# Stm32_sch.net
KiCad netlist of a schematic drawn in Altium Designer
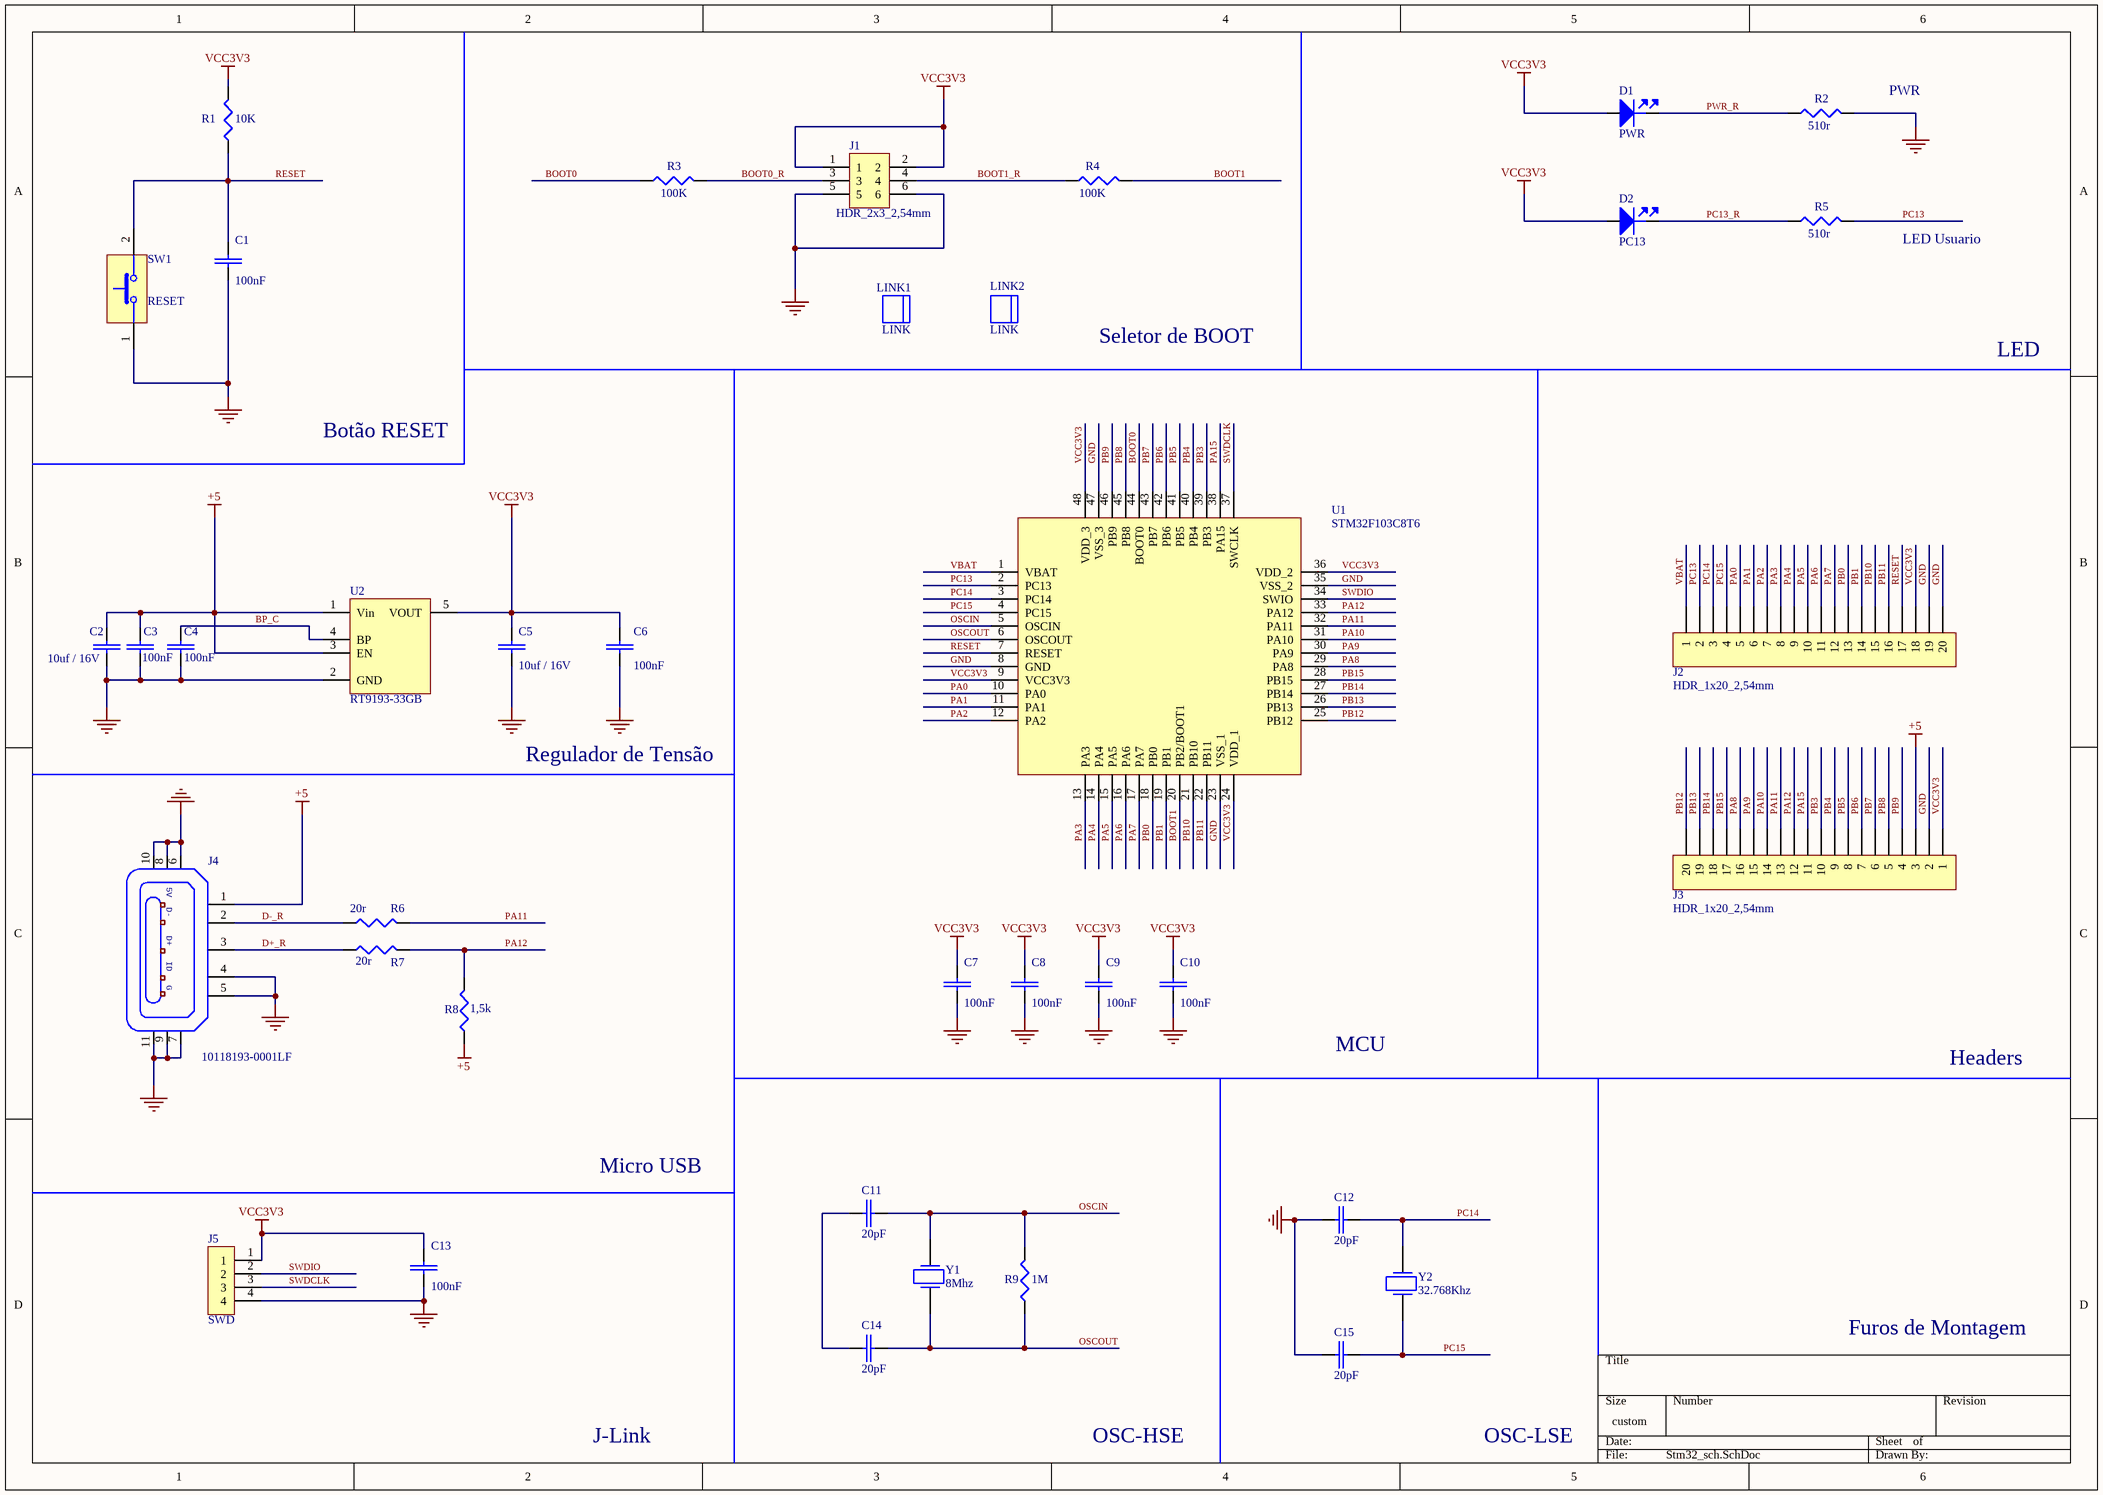
[diagram p0: Stm32_sch.SchDoc]

(export (version "E")
  (design (tool "Eeschema 10.0.6"))
  (components
    (comp (ref "C1")
      (value "100nF")
      (footprint "CP-0603")
      (description "Multilayer Ceramic Capacitors (MLCC) - SMD/SMT 50volts 0.1uF X7R 10%")
      (fields
        (field (name "MANUFACTURER") "KEMET")
        (field (name "MANUFACTURER PART NUMBER") "C0603C104K5RACTU")
      )
      (libsource (lib "Stm32_lib") (part "C-0603_100nF"))
    )
    (comp (ref "C2")
      (value "10uf / 16V")
      (footprint "CP_0805")
      (fields
        (field (name "MANUFACTURER") "TDK")
        (field (name "MANUFACTURER PART NUMBER") "C2012X5R1C106M085AC")
        (field (name "TOLERANCE") "20%")
      )
      (libsource (lib "Stm32_lib") (part "C-0805 10uF / 16V"))
    )
    (comp (ref "C3")
      (value "100nF")
      (footprint "CP-0603")
      (description "Multilayer Ceramic Capacitors (MLCC) - SMD/SMT 50volts 0.1uF X7R 10%")
      (fields
        (field (name "MANUFACTURER") "KEMET")
        (field (name "MANUFACTURER PART NUMBER") "C0603C104K5RACTU")
      )
      (libsource (lib "Stm32_lib") (part "C-0603_100nF"))
    )
    (comp (ref "C4")
      (value "100nF")
      (footprint "CP-0603")
      (description "Multilayer Ceramic Capacitors (MLCC) - SMD/SMT 50volts 0.1uF X7R 10%")
      (fields
        (field (name "MANUFACTURER") "KEMET")
        (field (name "MANUFACTURER PART NUMBER") "C0603C104K5RACTU")
      )
      (libsource (lib "Stm32_lib") (part "C-0603_100nF"))
    )
    (comp (ref "C5")
      (value "10uf / 16V")
      (footprint "CP_0805")
      (fields
        (field (name "MANUFACTURER") "TDK")
        (field (name "MANUFACTURER PART NUMBER") "C2012X5R1C106M085AC")
        (field (name "TOLERANCE") "20%")
      )
      (libsource (lib "Stm32_lib") (part "C-0805 10uF / 16V"))
    )
    (comp (ref "C6")
      (value "100nF")
      (footprint "CP-0603")
      (description "Multilayer Ceramic Capacitors (MLCC) - SMD/SMT 50volts 0.1uF X7R 10%")
      (fields
        (field (name "MANUFACTURER") "KEMET")
        (field (name "MANUFACTURER PART NUMBER") "C0603C104K5RACTU")
      )
      (libsource (lib "Stm32_lib") (part "C-0603_100nF"))
    )
    (comp (ref "C7")
      (value "100nF")
      (footprint "CP-0603")
      (description "Multilayer Ceramic Capacitors (MLCC) - SMD/SMT 50volts 0.1uF X7R 10%")
      (fields
        (field (name "MANUFACTURER") "KEMET")
        (field (name "MANUFACTURER PART NUMBER") "C0603C104K5RACTU")
      )
      (libsource (lib "Stm32_lib") (part "C-0603_100nF"))
    )
    (comp (ref "C8")
      (value "100nF")
      (footprint "CP-0603")
      (description "Multilayer Ceramic Capacitors (MLCC) - SMD/SMT 50volts 0.1uF X7R 10%")
      (fields
        (field (name "MANUFACTURER") "KEMET")
        (field (name "MANUFACTURER PART NUMBER") "C0603C104K5RACTU")
      )
      (libsource (lib "Stm32_lib") (part "C-0603_100nF"))
    )
    (comp (ref "C9")
      (value "100nF")
      (footprint "CP-0603")
      (description "Multilayer Ceramic Capacitors (MLCC) - SMD/SMT 50volts 0.1uF X7R 10%")
      (fields
        (field (name "MANUFACTURER") "KEMET")
        (field (name "MANUFACTURER PART NUMBER") "C0603C104K5RACTU")
      )
      (libsource (lib "Stm32_lib") (part "C-0603_100nF"))
    )
    (comp (ref "C10")
      (value "100nF")
      (footprint "CP-0603")
      (description "Multilayer Ceramic Capacitors (MLCC) - SMD/SMT 50volts 0.1uF X7R 10%")
      (fields
        (field (name "MANUFACTURER") "KEMET")
        (field (name "MANUFACTURER PART NUMBER") "C0603C104K5RACTU")
      )
      (libsource (lib "Stm32_lib") (part "C-0603_100nF"))
    )
    (comp (ref "C11")
      (value "20pF")
      (footprint "CP-0603")
      (description "Cap Ceramic 20pF 50V C0G 2% SMD 0603 125°C Paper T/R")
      (fields
        (field (name "MANUFACTURER") "KEMET")
        (field (name "MANUFACTURER PART NUMBER") "C0603C200G5GAC7867")
      )
      (libsource (lib "Stm32_lib") (part "C-0603_20pF"))
    )
    (comp (ref "C12")
      (value "20pF")
      (footprint "CP-0603")
      (description "Cap Ceramic 20pF 50V C0G 2% SMD 0603 125°C Paper T/R")
      (fields
        (field (name "MANUFACTURER") "KEMET")
        (field (name "MANUFACTURER PART NUMBER") "C0603C200G5GAC7867")
      )
      (libsource (lib "Stm32_lib") (part "C-0603_20pF"))
    )
    (comp (ref "C13")
      (value "100nF")
      (footprint "CP-0603")
      (description "Multilayer Ceramic Capacitors (MLCC) - SMD/SMT 50volts 0.1uF X7R 10%")
      (fields
        (field (name "MANUFACTURER") "KEMET")
        (field (name "MANUFACTURER PART NUMBER") "C0603C104K5RACTU")
      )
      (libsource (lib "Stm32_lib") (part "C-0603_100nF"))
    )
    (comp (ref "C14")
      (value "20pF")
      (footprint "CP-0603")
      (description "Cap Ceramic 20pF 50V C0G 2% SMD 0603 125°C Paper T/R")
      (fields
        (field (name "MANUFACTURER") "KEMET")
        (field (name "MANUFACTURER PART NUMBER") "C0603C200G5GAC7867")
      )
      (libsource (lib "Stm32_lib") (part "C-0603_20pF"))
    )
    (comp (ref "C15")
      (value "20pF")
      (footprint "CP-0603")
      (description "Cap Ceramic 20pF 50V C0G 2% SMD 0603 125°C Paper T/R")
      (fields
        (field (name "MANUFACTURER") "KEMET")
        (field (name "MANUFACTURER PART NUMBER") "C0603C200G5GAC7867")
      )
      (libsource (lib "Stm32_lib") (part "C-0603_20pF"))
    )
    (comp (ref "D1")
      (value "PWR")
      (footprint "LED_Green")
      (description "LED Uni-Color Green 2-Pin Chip 0603(1608Metric) T/R")
      (fields
        (field (name "MANUFACTURER") "Osram Opto")
        (field (name "MANUFACTURER PART NUMBER") "LG Q396-PS-35")
      )
      (libsource (lib "Stm32_lib") (part "LED_Green"))
    )
    (comp (ref "D2")
      (value "PC13")
      (footprint "LED_Orange")
      (description "Smartled Orange Lc")
      (fields
        (field (name "MANUFACTURER") "Osram Opto")
        (field (name "MANUFACTURER PART NUMBER") "LOL29K-H2K1-24-Z")
      )
      (libsource (lib "Stm32_lib") (part "LED_Orange"))
    )
    (comp (ref "J1")
      (value "HDR_2x3_2,54mm")
      (footprint "Header Male 2x3 2,54mm")
      (description "2.54mm (0.1\") Pitch DIL Vertical PC Tail Pin Header, 8.5mm mating pin height, tin, 3+3 contacts")
      (fields (field (name "MANUFACTURER") "Harwin") (field (name "MANUFACTURER PART NUMBER") "M20-9970346"))
      (libsource (lib "Stm32_lib") (part "HDR_2x3_2,54mm"))
    )
    (comp (ref "J2")
      (value "HDR_1x20_2,54mm")
      (footprint "HDR_1x20_2,54mm")
      (description "2.54mm (0.1\") Pitch SIL Vertical PC Tail Pin Header, 6.1mm mating pin height, tin, 20 contacts")
      (fields (field (name "MANUFACTURER") "Harwin") (field (name "MANUFACTURER PART NUMBER") "M20-9992046"))
      (libsource (lib "Stm32_lib") (part "HDR_1x20_p1"))
    )
    (comp (ref "J3")
      (value "HDR_1x20_2,54mm")
      (footprint "HDR2_1x20_2,54mm")
      (description "2.54mm (0.1\") Pitch SIL Vertical PC Tail Pin Header, 6.1mm mating pin height, tin, 20 contacts")
      (fields (field (name "MANUFACTURER") "Harwin") (field (name "MANUFACTURER PART NUMBER") "M20-9992046"))
      (libsource (lib "Stm32_lib") (part "HDR_1x20_p2"))
    )
    (comp (ref "J4")
      (value "10118193-0001LF")
      (footprint "Micro-Usb")
      (description "FCI Right Angle Surface Mount Mount Female USB Connector; 100 V ac; 1.8A")
      (fields (field (name "MANUFACTURER") "Amphenol ICC / FCI"))
      (libsource (lib "Stm32_lib") (part "Micro-Usb"))
    )
    (comp (ref "J5")
      (value "SWD")
      (footprint "HDR_M 1x4 2.54mm")
      (description "Conn Unshrouded Header HDR 4 POS 2.54mm Solder ST Top Entry Thru-Hole T/R")
      (fields
        (field (name "MANUFACTURER") "Amphenol ICC / FCI")
        (field (name "MANUFACTURER PART NUMBER") "77311-462K04LF")
      )
      (libsource (lib "Stm32_lib") (part "HDR_1x4_2.54mm"))
    )
    (comp (ref "LINK1")
      (value "LINK")
      (description "2 Position 2.54 mm Centerline Single Circuit Open Top Jumper")
      (fields
        (field (name "MANUFACTURER") "Sullins")
        (field (name "MANUFACTURER PART NUMBER") "QPC02SXGN-RC")
      )
      (libsource (lib "Stm32_lib") (part "COMM_Jumper"))
    )
    (comp (ref "LINK2")
      (value "LINK")
      (description "2 Position 2.54 mm Centerline Single Circuit Open Top Jumper")
      (fields
        (field (name "MANUFACTURER") "Sullins")
        (field (name "MANUFACTURER PART NUMBER") "QPC02SXGN-RC")
      )
      (libsource (lib "Stm32_lib") (part "COMM_Jumper"))
    )
    (comp (ref "R1")
      (value "10K")
      (footprint "R-0603")
      (description "Res Thin Film 0603 10K Ohm 0.5% 0.1W(1/10W) ±50ppm/C Epoxy SMD T/R")
      (fields
        (field (name "MANUFACTURER") "Yageo")
        (field (name "MANUFACTURER PART NUMBER") "RT0603DRE0710KL")
      )
      (libsource (lib "Stm32_lib") (part "R_0603_10K"))
    )
    (comp (ref "R2")
      (value "510r")
      (footprint "R-0603")
      (description "Res Thick Film 0603 510 Ohm 1% 1/10W 100ppm/C Molded SMD Paper T/R")
      (fields
        (field (name "MANUFACTURER") "Yageo")
        (field (name "MANUFACTURER PART NUMBER") "RC0603FR-07510RL")
      )
      (libsource (lib "Stm32_lib") (part "R_0603_510r"))
    )
    (comp (ref "R3")
      (value "100K")
      (footprint "R-0603")
      (description "RES SMD 100K OHM 1% 1/10W 0603")
      (fields
        (field (name "MANUFACTURER") "Yageo")
        (field (name "MANUFACTURER PART NUMBER") "RC0603FR-07100KL")
      )
      (libsource (lib "Stm32_lib") (part "R_0603_100K"))
    )
    (comp (ref "R4")
      (value "100K")
      (footprint "R-0603")
      (description "RES SMD 100K OHM 1% 1/10W 0603")
      (fields
        (field (name "MANUFACTURER") "Yageo")
        (field (name "MANUFACTURER PART NUMBER") "RC0603FR-07100KL")
      )
      (libsource (lib "Stm32_lib") (part "R_0603_100K"))
    )
    (comp (ref "R5")
      (value "510r")
      (footprint "R-0603")
      (description "Res Thick Film 0603 510 Ohm 1% 1/10W 100ppm/C Molded SMD Paper T/R")
      (fields
        (field (name "MANUFACTURER") "Yageo")
        (field (name "MANUFACTURER PART NUMBER") "RC0603FR-07510RL")
      )
      (libsource (lib "Stm32_lib") (part "R_0603_510r"))
    )
    (comp (ref "R6")
      (value "20r")
      (footprint "R-0603")
      (description "Res Thick Film 0603 20 Ohm 1% 0.1W(1/10W) ±100ppm/C Pad SMD T/R")
      (fields
        (field (name "MANUFACTURER") "Yageo")
        (field (name "MANUFACTURER PART NUMBER") "RC0603FR-0720RL")
      )
      (libsource (lib "Stm32_lib") (part "R_0603_20r"))
    )
    (comp (ref "R7")
      (value "20r")
      (footprint "R-0603")
      (description "Res Thick Film 0603 20 Ohm 1% 0.1W(1/10W) ±100ppm/C Pad SMD T/R")
      (fields
        (field (name "MANUFACTURER") "Yageo")
        (field (name "MANUFACTURER PART NUMBER") "RC0603FR-0720RL")
      )
      (libsource (lib "Stm32_lib") (part "R_0603_20r"))
    )
    (comp (ref "R8")
      (value "1,5k")
      (footprint "R-0603")
      (description "Res Thin Film 0603 1.5K Ohm 0.1% 1/10W ±25ppm/°C 0.01% Molded SMD SMD Waffle Pack")
      (fields
        (field (name "MANUFACTURER") "Vishay Dale")
        (field (name "MANUFACTURER PART NUMBER") "M55342E12B1B50RWS")
      )
      (libsource (lib "Stm32_lib") (part "R_0603_1,5k"))
    )
    (comp (ref "R9")
      (value "1M")
      (footprint "R-0603")
      (description "Res Thick Film 0603 1M Ohm 1% 1/10W ±100ppm/°C Molded SMD Paper T/R")
      (fields
        (field (name "MANUFACTURER") "Yageo")
        (field (name "MANUFACTURER PART NUMBER") "RC0603FR-071ML")
      )
      (libsource (lib "Stm32_lib") (part "R_0603_1M"))
    )
    (comp (ref "SW1")
      (value "RESET")
      (footprint "Push Button")
      (description "Switch Tactile N.O. SPST Rectangular Button F-Lead 0.05A 12VDC 2.45N SMD T/R")
      (fields
        (field (name "MANUFACTURER") "ITT C&K")
        (field (name "MANUFACTURER PART NUMBER") "PTS636SK25FSMTRLFS")
      )
      (libsource (lib "Stm32_lib") (part "Button N/O"))
    )
    (comp (ref "U1")
      (value "STM32F103C8T6")
      (footprint "Stm32f1")
      (description "IC MCU 32BIT 64KB FLASH 48LQFP")
      (fields (field (name "MANUFACTURER") "STMicroelectronics"))
      (libsource (lib "Stm32_lib") (part "STM32F103C8T6"))
    )
    (comp (ref "U2")
      (value "RT9193-33GB")
      (footprint "SOT_23_5")
      (description "IC REG LDO 3.3V 0.3A SOT23-5")
      (fields (field (name "MANUFACTURER") "Richtek"))
      (libsource (lib "Stm32_lib") (part "RT9193-33GB"))
    )
    (comp (ref "Y1")
      (value "8Mhz")
      (footprint "CK_8Mhz")
      (description "Crystal 8MHz ±20ppm (Tol) ±50ppm (Stability) 18pF FUND 80Ohm 2-Pin HC-49/US Thru-Hole Bulk")
      (fields
        (field (name "MANUFACTURER") "Abracon")
        (field (name "MANUFACTURER PART NUMBER") "ABL-8.000MHZ-B2")
      )
      (libsource (lib "Stm32_lib") (part "CK_8Mhz"))
    )
    (comp (ref "Y2")
      (value "32.768Khz")
      (footprint "CK_32.768Khz")
      (description "Crystal, Plastic Molded 32.768Khz, 6Pf, 10Ppm-40+85C, 8 X 3.8 X 2.5 Rohs Compliant: Yes")
      (fields
        (field (name "MANUFACTURER") "Abracon")
        (field (name "MANUFACTURER PART NUMBER") "ABS25-32.768KHZ-6-1-T")
      )
      (libsource (lib "Stm32_lib") (part "CK_32.768Khz"))
    )
  )
  (nets
    (net (code "1") (name "+5") (class "Default")
      (node (ref "C2") (pin "2") (pinfunction "2_2") (pintype "passive"))
      (node (ref "C3") (pin "2") (pinfunction "2_2") (pintype "passive"))
      (node (ref "J3") (pin "3") (pinfunction "3_3") (pintype "passive"))
      (node (ref "J4") (pin "1") (pinfunction "1_1") (pintype "passive"))
      (node (ref "R8") (pin "1") (pinfunction "1_1") (pintype "passive"))
      (node (ref "U2") (pin "1") (pinfunction "Vin_1") (pintype "passive"))
      (node (ref "U2") (pin "3") (pinfunction "EN_3") (pintype "passive"))
    )
    (net (code "2") (name "/BOOT0") (class "Default")
      (node (ref "R3") (pin "1") (pinfunction "1_1") (pintype "passive"))
      (node (ref "U1") (pin "44") (pinfunction "BOOT0_44") (pintype "passive"))
    )
    (net (code "3") (name "/BOOT0_R") (class "Default")
      (node (ref "J1") (pin "3") (pinfunction "3_3") (pintype "passive"))
      (node (ref "R3") (pin "2") (pinfunction "2_2") (pintype "passive"))
    )
    (net (code "4") (name "/BOOT1") (class "Default")
      (node (ref "R4") (pin "2") (pinfunction "2_2") (pintype "passive"))
      (node (ref "U1") (pin "20") (pinfunction "PB2/BOOT1_20") (pintype "passive"))
    )
    (net (code "5") (name "/BOOT1_R") (class "Default")
      (node (ref "J1") (pin "4") (pinfunction "4_4") (pintype "passive"))
      (node (ref "R4") (pin "1") (pinfunction "1_1") (pintype "passive"))
    )
    (net (code "6") (name "/BP_C") (class "Default")
      (node (ref "C4") (pin "2") (pinfunction "2_2") (pintype "passive"))
      (node (ref "U2") (pin "4") (pinfunction "BP_4") (pintype "passive"))
    )
    (net (code "7") (name "/D+_R") (class "Default")
      (node (ref "J4") (pin "3") (pinfunction "3_3") (pintype "passive"))
      (node (ref "R7") (pin "1") (pinfunction "1_1") (pintype "passive"))
    )
    (net (code "8") (name "/D-_R") (class "Default")
      (node (ref "J4") (pin "2") (pinfunction "2_2") (pintype "passive"))
      (node (ref "R6") (pin "1") (pinfunction "1_1") (pintype "passive"))
    )
    (net (code "9") (name "/OSCIN") (class "Default")
      (node (ref "C11") (pin "2") (pinfunction "2_2") (pintype "passive"))
      (node (ref "R9") (pin "2") (pinfunction "2_2") (pintype "passive"))
      (node (ref "U1") (pin "5") (pinfunction "OSCIN_5") (pintype "passive"))
      (node (ref "Y1") (pin "2") (pinfunction "2_2") (pintype "passive"))
    )
    (net (code "10") (name "/OSCOUT") (class "Default")
      (node (ref "C14") (pin "2") (pinfunction "2_2") (pintype "passive"))
      (node (ref "R9") (pin "1") (pinfunction "1_1") (pintype "passive"))
      (node (ref "U1") (pin "6") (pinfunction "OSCOUT_6") (pintype "passive"))
      (node (ref "Y1") (pin "1") (pinfunction "1_1") (pintype "passive"))
    )
    (net (code "11") (name "/PA0") (class "Default")
      (node (ref "J2") (pin "5") (pinfunction "5_5") (pintype "passive"))
      (node (ref "U1") (pin "10") (pinfunction "PA0_10") (pintype "passive"))
    )
    (net (code "12") (name "/PA1") (class "Default")
      (node (ref "J2") (pin "6") (pinfunction "6_6") (pintype "passive"))
      (node (ref "U1") (pin "11") (pinfunction "PA1_11") (pintype "passive"))
    )
    (net (code "13") (name "/PA2") (class "Default")
      (node (ref "J2") (pin "7") (pinfunction "7_7") (pintype "passive"))
      (node (ref "U1") (pin "12") (pinfunction "PA2_12") (pintype "passive"))
    )
    (net (code "14") (name "/PA3") (class "Default")
      (node (ref "J2") (pin "8") (pinfunction "8_8") (pintype "passive"))
      (node (ref "U1") (pin "13") (pinfunction "PA3_13") (pintype "passive"))
    )
    (net (code "15") (name "/PA4") (class "Default")
      (node (ref "J2") (pin "9") (pinfunction "9_9") (pintype "passive"))
      (node (ref "U1") (pin "14") (pinfunction "PA4_14") (pintype "passive"))
    )
    (net (code "16") (name "/PA5") (class "Default")
      (node (ref "J2") (pin "10") (pinfunction "10_10") (pintype "passive"))
      (node (ref "U1") (pin "15") (pinfunction "PA5_15") (pintype "passive"))
    )
    (net (code "17") (name "/PA6") (class "Default")
      (node (ref "J2") (pin "11") (pinfunction "11_11") (pintype "passive"))
      (node (ref "U1") (pin "16") (pinfunction "PA6_16") (pintype "passive"))
    )
    (net (code "18") (name "/PA7") (class "Default")
      (node (ref "J2") (pin "12") (pinfunction "12_12") (pintype "passive"))
      (node (ref "U1") (pin "17") (pinfunction "PA7_17") (pintype "passive"))
    )
    (net (code "19") (name "/PA8") (class "Default")
      (node (ref "J3") (pin "16") (pinfunction "16_16") (pintype "passive"))
      (node (ref "U1") (pin "29") (pinfunction "PA8_29") (pintype "passive"))
    )
    (net (code "20") (name "/PA9") (class "Default")
      (node (ref "J3") (pin "15") (pinfunction "15_15") (pintype "passive"))
      (node (ref "U1") (pin "30") (pinfunction "PA9_30") (pintype "passive"))
    )
    (net (code "21") (name "/PA10") (class "Default")
      (node (ref "J3") (pin "14") (pinfunction "14_14") (pintype "passive"))
      (node (ref "U1") (pin "31") (pinfunction "PA10_31") (pintype "passive"))
    )
    (net (code "22") (name "/PA11") (class "Default")
      (node (ref "J3") (pin "13") (pinfunction "13_13") (pintype "passive"))
      (node (ref "R6") (pin "2") (pinfunction "2_2") (pintype "passive"))
      (node (ref "U1") (pin "32") (pinfunction "PA11_32") (pintype "passive"))
    )
    (net (code "23") (name "/PA12") (class "Default")
      (node (ref "J3") (pin "12") (pinfunction "12_12") (pintype "passive"))
      (node (ref "R7") (pin "2") (pinfunction "2_2") (pintype "passive"))
      (node (ref "R8") (pin "2") (pinfunction "2_2") (pintype "passive"))
      (node (ref "U1") (pin "33") (pinfunction "PA12_33") (pintype "passive"))
    )
    (net (code "24") (name "/PA15") (class "Default")
      (node (ref "J3") (pin "11") (pinfunction "11_11") (pintype "passive"))
      (node (ref "U1") (pin "38") (pinfunction "PA15_38") (pintype "passive"))
    )
    (net (code "25") (name "/PB0") (class "Default")
      (node (ref "J2") (pin "13") (pinfunction "13_13") (pintype "passive"))
      (node (ref "U1") (pin "18") (pinfunction "PB0_18") (pintype "passive"))
    )
    (net (code "26") (name "/PB1") (class "Default")
      (node (ref "J2") (pin "14") (pinfunction "14_14") (pintype "passive"))
      (node (ref "U1") (pin "19") (pinfunction "PB1_19") (pintype "passive"))
    )
    (net (code "27") (name "/PB3") (class "Default")
      (node (ref "J3") (pin "10") (pinfunction "10_10") (pintype "passive"))
      (node (ref "U1") (pin "39") (pinfunction "PB3_39") (pintype "passive"))
    )
    (net (code "28") (name "/PB4") (class "Default")
      (node (ref "J3") (pin "9") (pinfunction "9_9") (pintype "passive"))
      (node (ref "U1") (pin "40") (pinfunction "PB4_40") (pintype "passive"))
    )
    (net (code "29") (name "/PB5") (class "Default")
      (node (ref "J3") (pin "8") (pinfunction "8_8") (pintype "passive"))
      (node (ref "U1") (pin "41") (pinfunction "PB5_41") (pintype "passive"))
    )
    (net (code "30") (name "/PB6") (class "Default")
      (node (ref "J3") (pin "7") (pinfunction "7_7") (pintype "passive"))
      (node (ref "U1") (pin "42") (pinfunction "PB6_42") (pintype "passive"))
    )
    (net (code "31") (name "/PB7") (class "Default")
      (node (ref "J3") (pin "6") (pinfunction "6_6") (pintype "passive"))
      (node (ref "U1") (pin "43") (pinfunction "PB7_43") (pintype "passive"))
    )
    (net (code "32") (name "/PB8") (class "Default")
      (node (ref "J3") (pin "5") (pinfunction "5_5") (pintype "passive"))
      (node (ref "U1") (pin "45") (pinfunction "PB8_45") (pintype "passive"))
    )
    (net (code "33") (name "/PB9") (class "Default")
      (node (ref "J3") (pin "4") (pinfunction "4_4") (pintype "passive"))
      (node (ref "U1") (pin "46") (pinfunction "PB9_46") (pintype "passive"))
    )
    (net (code "34") (name "/PB10") (class "Default")
      (node (ref "J2") (pin "15") (pinfunction "15_15") (pintype "passive"))
      (node (ref "U1") (pin "21") (pinfunction "PB10_21") (pintype "passive"))
    )
    (net (code "35") (name "/PB11") (class "Default")
      (node (ref "J2") (pin "16") (pinfunction "16_16") (pintype "passive"))
      (node (ref "U1") (pin "22") (pinfunction "PB11_22") (pintype "passive"))
    )
    (net (code "36") (name "/PB12") (class "Default")
      (node (ref "J3") (pin "20") (pinfunction "20_20") (pintype "passive"))
      (node (ref "U1") (pin "25") (pinfunction "PB12_25") (pintype "passive"))
    )
    (net (code "37") (name "/PB13") (class "Default")
      (node (ref "J3") (pin "19") (pinfunction "19_19") (pintype "passive"))
      (node (ref "U1") (pin "26") (pinfunction "PB13_26") (pintype "passive"))
    )
    (net (code "38") (name "/PB14") (class "Default")
      (node (ref "J3") (pin "18") (pinfunction "18_18") (pintype "passive"))
      (node (ref "U1") (pin "27") (pinfunction "PB14_27") (pintype "passive"))
    )
    (net (code "39") (name "/PB15") (class "Default")
      (node (ref "J3") (pin "17") (pinfunction "17_17") (pintype "passive"))
      (node (ref "U1") (pin "28") (pinfunction "PB15_28") (pintype "passive"))
    )
    (net (code "40") (name "/PC13") (class "Default")
      (node (ref "J2") (pin "2") (pinfunction "2_2") (pintype "passive"))
      (node (ref "R5") (pin "2") (pinfunction "2_2") (pintype "passive"))
      (node (ref "U1") (pin "2") (pinfunction "PC13_2") (pintype "passive"))
    )
    (net (code "41") (name "/PC13_R") (class "Default")
      (node (ref "D2") (pin "1") (pinfunction "KAT_1") (pintype "passive"))
      (node (ref "R5") (pin "1") (pinfunction "1_1") (pintype "passive"))
    )
    (net (code "42") (name "/PC14") (class "Default")
      (node (ref "C12") (pin "2") (pinfunction "2_2") (pintype "passive"))
      (node (ref "J2") (pin "3") (pinfunction "3_3") (pintype "passive"))
      (node (ref "U1") (pin "3") (pinfunction "PC14_3") (pintype "passive"))
      (node (ref "Y2") (pin "2") (pinfunction "2_2") (pintype "passive"))
    )
    (net (code "43") (name "/PC15") (class "Default")
      (node (ref "C15") (pin "2") (pinfunction "2_2") (pintype "passive"))
      (node (ref "J2") (pin "4") (pinfunction "4_4") (pintype "passive"))
      (node (ref "U1") (pin "4") (pinfunction "PC15_4") (pintype "passive"))
      (node (ref "Y2") (pin "1") (pinfunction "1_1") (pintype "passive"))
    )
    (net (code "44") (name "/PWR_R") (class "Default")
      (node (ref "D1") (pin "1") (pinfunction "KAT_1") (pintype "passive"))
      (node (ref "R2") (pin "1") (pinfunction "1_1") (pintype "passive"))
    )
    (net (code "45") (name "/RESET") (class "Default")
      (node (ref "C1") (pin "2") (pinfunction "2_2") (pintype "passive"))
      (node (ref "J2") (pin "17") (pinfunction "17_17") (pintype "passive"))
      (node (ref "R1") (pin "1") (pinfunction "1_1") (pintype "passive"))
      (node (ref "SW1") (pin "2") (pinfunction "2_2") (pintype "passive"))
      (node (ref "U1") (pin "7") (pinfunction "RESET_7") (pintype "passive"))
    )
    (net (code "46") (name "/SWDCLK") (class "Default")
      (node (ref "J5") (pin "3") (pinfunction "3_3") (pintype "passive"))
      (node (ref "U1") (pin "37") (pinfunction "SWCLK_37") (pintype "passive"))
    )
    (net (code "47") (name "/SWDIO") (class "Default")
      (node (ref "J5") (pin "2") (pinfunction "2_2") (pintype "passive"))
      (node (ref "U1") (pin "34") (pinfunction "SWIO_34") (pintype "passive"))
    )
    (net (code "48") (name "/VBAT") (class "Default")
      (node (ref "J2") (pin "1") (pinfunction "1_1") (pintype "passive"))
      (node (ref "U1") (pin "1") (pinfunction "VBAT_1") (pintype "passive"))
    )
    (net (code "49") (name "GND") (class "Default")
      (node (ref "C1") (pin "1") (pinfunction "1_1") (pintype "passive"))
      (node (ref "C10") (pin "1") (pinfunction "1_1") (pintype "passive"))
      (node (ref "C12") (pin "1") (pinfunction "1_1") (pintype "passive"))
      (node (ref "C13") (pin "1") (pinfunction "1_1") (pintype "passive"))
      (node (ref "C15") (pin "1") (pinfunction "1_1") (pintype "passive"))
      (node (ref "C2") (pin "1") (pinfunction "1_1") (pintype "passive"))
      (node (ref "C3") (pin "1") (pinfunction "1_1") (pintype "passive"))
      (node (ref "C4") (pin "1") (pinfunction "1_1") (pintype "passive"))
      (node (ref "C5") (pin "1") (pinfunction "1_1") (pintype "passive"))
      (node (ref "C6") (pin "1") (pinfunction "1_1") (pintype "passive"))
      (node (ref "C7") (pin "1") (pinfunction "1_1") (pintype "passive"))
      (node (ref "C8") (pin "1") (pinfunction "1_1") (pintype "passive"))
      (node (ref "C9") (pin "1") (pinfunction "1_1") (pintype "passive"))
      (node (ref "J1") (pin "5") (pinfunction "5_5") (pintype "passive"))
      (node (ref "J1") (pin "6") (pinfunction "6_6") (pintype "passive"))
      (node (ref "J2") (pin "19") (pinfunction "19_19") (pintype "passive"))
      (node (ref "J2") (pin "20") (pinfunction "20_20") (pintype "passive"))
      (node (ref "J3") (pin "2") (pinfunction "2_2") (pintype "passive"))
      (node (ref "J4") (pin "10") (pinfunction "10_10") (pintype "passive"))
      (node (ref "J4") (pin "11") (pinfunction "11_11") (pintype "passive"))
      (node (ref "J4") (pin "4") (pinfunction "4_4") (pintype "passive"))
      (node (ref "J4") (pin "5") (pinfunction "5_5") (pintype "passive"))
      (node (ref "J4") (pin "6") (pinfunction "6_6") (pintype "passive"))
      (node (ref "J4") (pin "7") (pinfunction "7_7") (pintype "passive"))
      (node (ref "J4") (pin "8") (pinfunction "8_8") (pintype "passive"))
      (node (ref "J4") (pin "9") (pinfunction "9_9") (pintype "passive"))
      (node (ref "J5") (pin "4") (pinfunction "4_4") (pintype "passive"))
      (node (ref "R2") (pin "2") (pinfunction "2_2") (pintype "passive"))
      (node (ref "SW1") (pin "1") (pinfunction "1_1") (pintype "passive"))
      (node (ref "U1") (pin "23") (pinfunction "VSS_1_23") (pintype "passive"))
      (node (ref "U1") (pin "35") (pinfunction "VSS_2_35") (pintype "passive"))
      (node (ref "U1") (pin "47") (pinfunction "VSS_3_47") (pintype "passive"))
      (node (ref "U1") (pin "8") (pinfunction "GND_8") (pintype "passive"))
      (node (ref "U2") (pin "2") (pinfunction "GND_2") (pintype "passive"))
    )
    (net (code "50") (name "Net-(C11-Pad1)") (class "Default")
      (node (ref "C11") (pin "1") (pinfunction "1_1") (pintype "passive"))
      (node (ref "C14") (pin "1") (pinfunction "1_1") (pintype "passive"))
    )
    (net (code "51") (name "VCC3V3") (class "Default")
      (node (ref "C10") (pin "2") (pinfunction "2_2") (pintype "passive"))
      (node (ref "C13") (pin "2") (pinfunction "2_2") (pintype "passive"))
      (node (ref "C5") (pin "2") (pinfunction "2_2") (pintype "passive"))
      (node (ref "C6") (pin "2") (pinfunction "2_2") (pintype "passive"))
      (node (ref "C7") (pin "2") (pinfunction "2_2") (pintype "passive"))
      (node (ref "C8") (pin "2") (pinfunction "2_2") (pintype "passive"))
      (node (ref "C9") (pin "2") (pinfunction "2_2") (pintype "passive"))
      (node (ref "D1") (pin "2") (pinfunction "ANODE_2") (pintype "passive"))
      (node (ref "D2") (pin "2") (pinfunction "ANODE_2") (pintype "passive"))
      (node (ref "J1") (pin "1") (pinfunction "1_1") (pintype "passive"))
      (node (ref "J1") (pin "2") (pinfunction "2_2") (pintype "passive"))
      (node (ref "J2") (pin "18") (pinfunction "18_18") (pintype "passive"))
      (node (ref "J3") (pin "1") (pinfunction "1_1") (pintype "passive"))
      (node (ref "J5") (pin "1") (pinfunction "1_1") (pintype "passive"))
      (node (ref "R1") (pin "2") (pinfunction "2_2") (pintype "passive"))
      (node (ref "U1") (pin "24") (pinfunction "VDD_1_24") (pintype "passive"))
      (node (ref "U1") (pin "36") (pinfunction "VDD_2_36") (pintype "passive"))
      (node (ref "U1") (pin "48") (pinfunction "VDD_3_48") (pintype "passive"))
      (node (ref "U1") (pin "9") (pinfunction "VCC3V3_9") (pintype "passive"))
      (node (ref "U2") (pin "5") (pinfunction "VOUT_5") (pintype "passive"))
    )
  )
)
